# Sch.net
KiCad netlist of a schematic drawn in Altium Designer
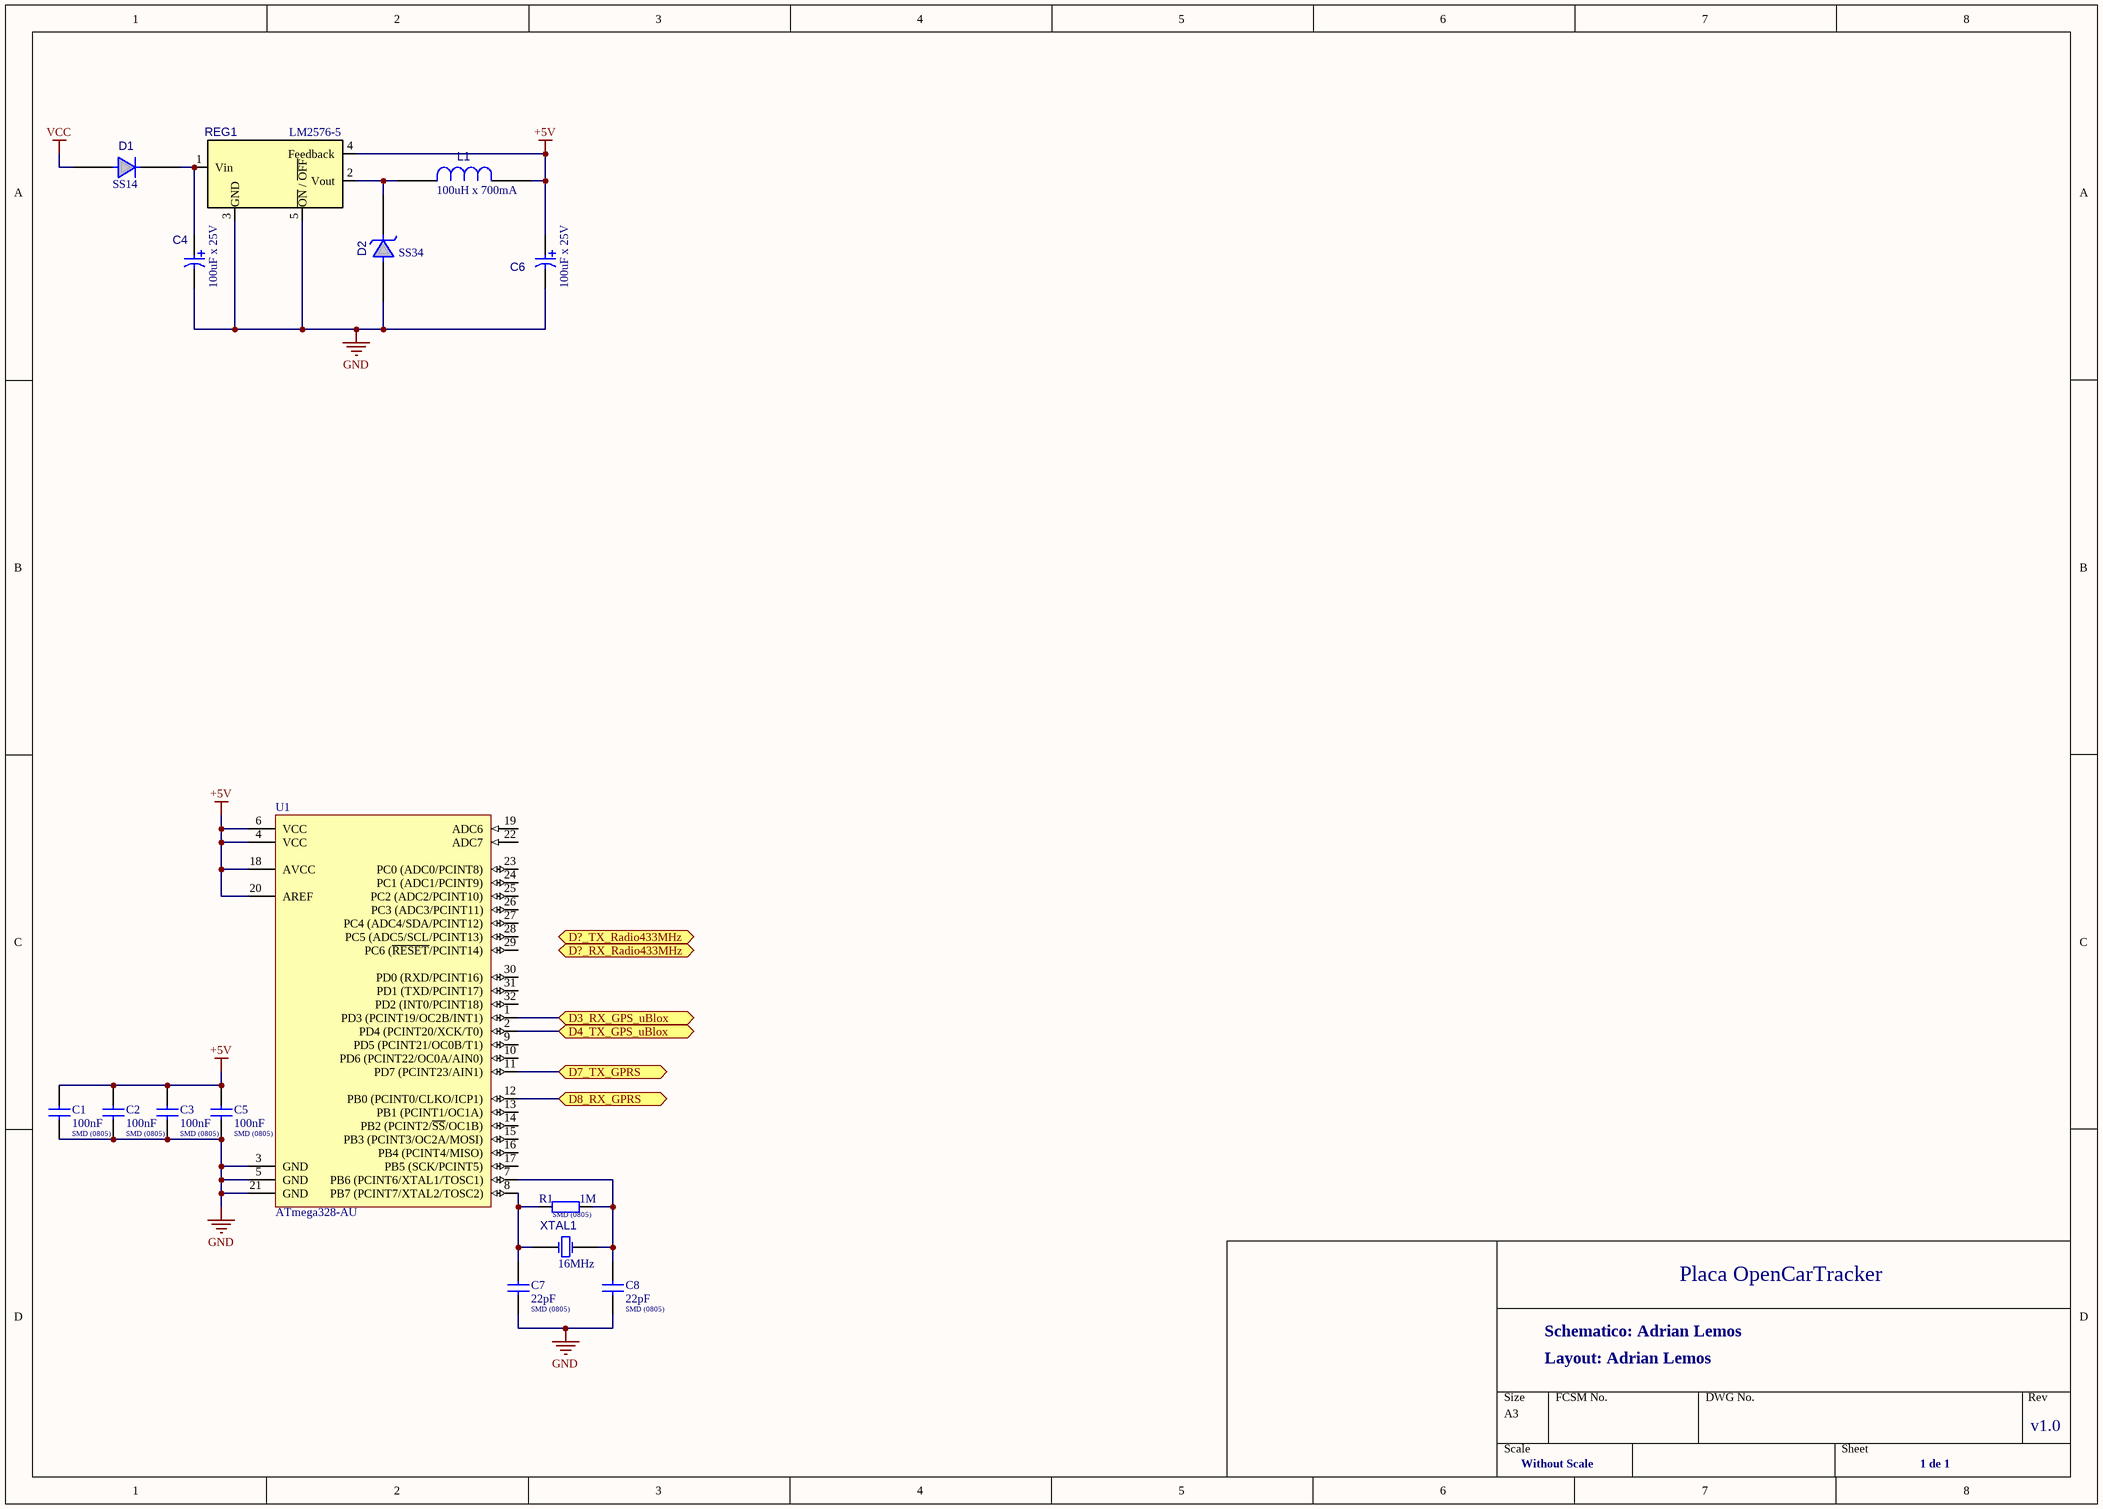
[diagram p0: Sch_.SchDoc]

(export (version "E")
  (design (tool "Eeschema 10.0.6"))
  (components
    (comp (ref "C1")
      (value "Capacitor SMD")
      (footprint "CAP_0805")
      (fields (field (name "VALOR") "100nF") (field (name "ENCAPSULAMENTO") "SMD (0805)"))
      (libsource (lib "Altium_Library_Brasil") (part "Capacitor SMD"))
    )
    (comp (ref "C2")
      (value "Capacitor SMD")
      (footprint "CAP_0805")
      (fields (field (name "VALOR") "100nF") (field (name "ENCAPSULAMENTO") "SMD (0805)"))
      (libsource (lib "Altium_Library_Brasil") (part "Capacitor SMD"))
    )
    (comp (ref "C3")
      (value "Capacitor SMD")
      (footprint "CAP_0805")
      (fields (field (name "VALOR") "100nF") (field (name "ENCAPSULAMENTO") "SMD (0805)"))
      (libsource (lib "Altium_Library_Brasil") (part "Capacitor SMD"))
    )
    (comp (ref "C4")
      (value "Capacitor Eletrolitico")
      (footprint "CAPACITOR ELETROLITICO SMD")
      (fields (field (name "VALOR") "100uF x 25V"))
      (libsource (lib "Altium_Library_Brasil") (part "Capacitor Eletrolitico"))
    )
    (comp (ref "C5")
      (value "Capacitor SMD")
      (footprint "CAP_0805")
      (fields (field (name "VALOR") "100nF") (field (name "ENCAPSULAMENTO") "SMD (0805)"))
      (libsource (lib "Altium_Library_Brasil") (part "Capacitor SMD"))
    )
    (comp (ref "C6")
      (value "Capacitor Eletrolitico")
      (footprint "CAPACITOR ELETROLITICO SMD")
      (fields (field (name "VALOR") "100uF x 25V"))
      (libsource (lib "Altium_Library_Brasil") (part "Capacitor Eletrolitico"))
    )
    (comp (ref "C7")
      (value "Capacitor SMD")
      (footprint "CAP_0805")
      (fields (field (name "VALOR") "22pF") (field (name "ENCAPSULAMENTO") "SMD (0805)"))
      (libsource (lib "Altium_Library_Brasil") (part "Capacitor SMD"))
    )
    (comp (ref "C8")
      (value "Capacitor SMD")
      (footprint "CAP_0805")
      (fields (field (name "VALOR") "22pF") (field (name "ENCAPSULAMENTO") "SMD (0805)"))
      (libsource (lib "Altium_Library_Brasil") (part "Capacitor SMD"))
    )
    (comp (ref "D1")
      (value "DIODO_SS14_S1D")
      (footprint "DO214AC")
      (description "Diodo SMD Shottky")
      (fields (field (name "MODELO") "SS14"))
      (libsource (lib "Altium_Library_Brasil") (part "SS14 Schottky Diode"))
    )
    (comp (ref "D2")
      (value "SS34")
      (footprint "DO214AB")
      (description "DIODO-SCHOTTKY-SMD 3A 40V")
      (fields (field (name "MODELO") "SS34"))
      (libsource (lib "Altium_Library_Brasil") (part "SS34"))
    )
    (comp (ref "L1")
      (value "Indutor_700mA")
      (footprint "INDUTOR RADIAL 10.5MM")
      (description "IND200-CIRC")
      (fields (field (name "VALOR") "100uH x 700mA"))
      (libsource (lib "Altium_Library_Brasil") (part "Indutor_700mA"))
    )
    (comp (ref "R1")
      (value "Resistor SMD")
      (footprint "RES_0805")
      (fields (field (name "VALOR") "1M") (field (name "ENCAPSULAMENTO") "SMD (0805)"))
      (libsource (lib "Altium_Library_Brasil") (part "Resistor SMD"))
    )
    (comp (ref "REG1")
      (value "LM2576")
      (footprint "TO-263-5")
      (description "Regulador de Tensão LM2576")
      (fields (field (name "MODELO") "LM2576-5"))
      (libsource (lib "Altium_Library_Brasil") (part "LM2576"))
    )
    (comp (ref "U1")
      (value "ATmega328-AU")
      (footprint "TQFP32")
      (fields (field (name "MODELO") "ATmega328-AU"))
      (libsource (lib "Altium_Library_Brasil") (part "ATmega328-AU"))
    )
    (comp (ref "XTAL1")
      (value "CRISTAL-SMD-HC49S")
      (footprint "Cristal HC49S")
      (fields (field (name "VALOR") "16MHz"))
      (libsource (lib "Altium_Library_Brasil") (part "CRISTAL-SMD-HC49S"))
    )
  )
  (nets
    (net (code "1") (name "+5V") (class "Default")
      (node (ref "C1") (pin "2") (pinfunction "2_2") (pintype "passive"))
      (node (ref "C2") (pin "2") (pinfunction "2_2") (pintype "passive"))
      (node (ref "C3") (pin "2") (pinfunction "2_2") (pintype "passive"))
      (node (ref "C5") (pin "2") (pinfunction "2_2") (pintype "passive"))
      (node (ref "C6") (pin "1") (pinfunction "PLUS_1") (pintype "passive"))
      (node (ref "L1") (pin "1") (pintype "passive"))
      (node (ref "REG1") (pin "4") (pinfunction "Feedback_4") (pintype "passive"))
      (node (ref "U1") (pin "18") (pinfunction "AVCC_18") (pintype "power_in"))
      (node (ref "U1") (pin "20") (pinfunction "AREF_20") (pintype "passive"))
      (node (ref "U1") (pin "4") (pinfunction "VCC_4") (pintype "power_in"))
      (node (ref "U1") (pin "6") (pinfunction "VCC_6") (pintype "power_in"))
    )
    (net (code "2") (name "/D3_RX_GPS_uBlox") (class "Default")
      (node (ref "U1") (pin "1") (pinfunction "PD3_(PCINT19/OC2B/INT1)_1") (pintype "bidirectional"))
    )
    (net (code "3") (name "/D4_TX_GPS_uBlox") (class "Default")
      (node (ref "U1") (pin "2") (pinfunction "PD4_(PCINT20/XCK/T0)_2") (pintype "bidirectional"))
    )
    (net (code "4") (name "/D7_TX_GPRS") (class "Default")
      (node (ref "U1") (pin "11") (pinfunction "PD7_(PCINT23/AIN1)_11") (pintype "bidirectional"))
    )
    (net (code "5") (name "/D8_RX_GPRS") (class "Default")
      (node (ref "U1") (pin "12") (pinfunction "PB0_(PCINT0/CLKO/ICP1)_12") (pintype "bidirectional"))
    )
    (net (code "8") (name "GND") (class "Default")
      (node (ref "C1") (pin "1") (pinfunction "1_1") (pintype "passive"))
      (node (ref "C2") (pin "1") (pinfunction "1_1") (pintype "passive"))
      (node (ref "C3") (pin "1") (pinfunction "1_1") (pintype "passive"))
      (node (ref "C4") (pin "2") (pinfunction "MINUS_2") (pintype "passive"))
      (node (ref "C5") (pin "1") (pinfunction "1_1") (pintype "passive"))
      (node (ref "C6") (pin "2") (pinfunction "MINUS_2") (pintype "passive"))
      (node (ref "C7") (pin "1") (pinfunction "1_1") (pintype "passive"))
      (node (ref "C8") (pin "1") (pinfunction "1_1") (pintype "passive"))
      (node (ref "D2") (pin "1") (pinfunction "1_1") (pintype "passive"))
      (node (ref "REG1") (pin "3") (pinfunction "GND_3") (pintype "passive"))
      (node (ref "REG1") (pin "5") (pinfunction "~{ON}_/_~{OFF}_5") (pintype "passive"))
      (node (ref "U1") (pin "21") (pinfunction "GND_21") (pintype "power_in"))
      (node (ref "U1") (pin "3") (pinfunction "GND_3") (pintype "power_in"))
      (node (ref "U1") (pin "5") (pinfunction "GND_5") (pintype "power_in"))
    )
    (net (code "9") (name "Net-(C4-PLUS)") (class "Default")
      (node (ref "C4") (pin "1") (pinfunction "PLUS_1") (pintype "passive"))
      (node (ref "D1") (pin "1") (pinfunction "K_1") (pintype "passive"))
      (node (ref "REG1") (pin "1") (pinfunction "Vin_1") (pintype "passive"))
    )
    (net (code "10") (name "Net-(REG1-Vout)") (class "Default")
      (node (ref "D2") (pin "2") (pinfunction "2_2") (pintype "passive"))
      (node (ref "L1") (pin "2") (pintype "passive"))
      (node (ref "REG1") (pin "2") (pinfunction "Vout_2") (pintype "passive"))
    )
    (net (code "11") (name "Net-(U1-PB6_(PCINT6{slash}XTAL1{slash}TOSC1))") (class "Default")
      (node (ref "C8") (pin "2") (pinfunction "2_2") (pintype "passive"))
      (node (ref "R1") (pin "2") (pinfunction "2_2") (pintype "passive"))
      (node (ref "U1") (pin "7") (pinfunction "PB6_(PCINT6/XTAL1/TOSC1)_7") (pintype "bidirectional"))
      (node (ref "XTAL1") (pin "2") (pinfunction "OSC2_2") (pintype "passive"))
    )
    (net (code "12") (name "Net-(U1-PB7_(PCINT7{slash}XTAL2{slash}TOSC2))") (class "Default")
      (node (ref "C7") (pin "2") (pinfunction "2_2") (pintype "passive"))
      (node (ref "R1") (pin "1") (pinfunction "1_1") (pintype "passive"))
      (node (ref "U1") (pin "8") (pinfunction "PB7_(PCINT7/XTAL2/TOSC2)_8") (pintype "bidirectional"))
      (node (ref "XTAL1") (pin "1") (pinfunction "OSC1_1") (pintype "passive"))
    )
    (net (code "13") (name "VCC") (class "Default")
      (node (ref "D1") (pin "2") (pinfunction "A_2") (pintype "passive"))
    )
    (net (code "14") (name "unconnected-(U1-ADC6-Pad19)") (class "Default")
      (node (ref "U1") (pin "19") (pinfunction "ADC6_19") (pintype "input"))
    )
    (net (code "15") (name "unconnected-(U1-ADC7-Pad22)") (class "Default")
      (node (ref "U1") (pin "22") (pinfunction "ADC7_22") (pintype "input"))
    )
    (net (code "16") (name "unconnected-(U1-PB1_(PCINT1{slash}OC1A)-Pad13)") (class "Default")
      (node (ref "U1") (pin "13") (pinfunction "PB1_(PCINT1/OC1A)_13") (pintype "bidirectional"))
    )
    (net (code "17") (name "unconnected-(U1-PB2_(PCINT2{slash}~{SS}{slash}OC1B)-Pad14)") (class "Default")
      (node (ref "U1") (pin "14") (pinfunction "PB2_(PCINT2/~{SS}/OC1B)_14") (pintype "bidirectional"))
    )
    (net (code "18") (name "unconnected-(U1-PB3_(PCINT3{slash}OC2A{slash}MOSI)-Pad15)") (class "Default")
      (node (ref "U1") (pin "15") (pinfunction "PB3_(PCINT3/OC2A/MOSI)_15") (pintype "bidirectional"))
    )
    (net (code "19") (name "unconnected-(U1-PB4_(PCINT4{slash}MISO)-Pad16)") (class "Default")
      (node (ref "U1") (pin "16") (pinfunction "PB4_(PCINT4/MISO)_16") (pintype "bidirectional"))
    )
    (net (code "20") (name "unconnected-(U1-PB5_(SCK{slash}PCINT5)-Pad17)") (class "Default")
      (node (ref "U1") (pin "17") (pinfunction "PB5_(SCK/PCINT5)_17") (pintype "bidirectional"))
    )
    (net (code "21") (name "unconnected-(U1-PC0_(ADC0{slash}PCINT8)-Pad23)") (class "Default")
      (node (ref "U1") (pin "23") (pinfunction "PC0_(ADC0/PCINT8)_23") (pintype "bidirectional"))
    )
    (net (code "22") (name "unconnected-(U1-PC1_(ADC1{slash}PCINT9)-Pad24)") (class "Default")
      (node (ref "U1") (pin "24") (pinfunction "PC1_(ADC1/PCINT9)_24") (pintype "bidirectional"))
    )
    (net (code "23") (name "unconnected-(U1-PC2_(ADC2{slash}PCINT10)-Pad25)") (class "Default")
      (node (ref "U1") (pin "25") (pinfunction "PC2_(ADC2/PCINT10)_25") (pintype "bidirectional"))
    )
    (net (code "24") (name "unconnected-(U1-PC3_(ADC3{slash}PCINT11)-Pad26)") (class "Default")
      (node (ref "U1") (pin "26") (pinfunction "PC3_(ADC3/PCINT11)_26") (pintype "bidirectional"))
    )
    (net (code "25") (name "unconnected-(U1-PC4_(ADC4{slash}SDA{slash}PCINT12)-Pad27)") (class "Default")
      (node (ref "U1") (pin "27") (pinfunction "PC4_(ADC4/SDA/PCINT12)_27") (pintype "bidirectional"))
    )
    (net (code "26") (name "unconnected-(U1-PC5_(ADC5{slash}SCL{slash}PCINT13)-Pad28)") (class "Default")
      (node (ref "U1") (pin "28") (pinfunction "PC5_(ADC5/SCL/PCINT13)_28") (pintype "bidirectional"))
    )
    (net (code "27") (name "unconnected-(U1-PC6_(~{RESET}{slash}PCINT14)-Pad29)") (class "Default")
      (node (ref "U1") (pin "29") (pinfunction "PC6_(~{RESET}/PCINT14)_29") (pintype "bidirectional"))
    )
    (net (code "28") (name "unconnected-(U1-PD0_(RXD{slash}PCINT16)-Pad30)") (class "Default")
      (node (ref "U1") (pin "30") (pinfunction "PD0_(RXD/PCINT16)_30") (pintype "bidirectional"))
    )
    (net (code "29") (name "unconnected-(U1-PD1_(TXD{slash}PCINT17)-Pad31)") (class "Default")
      (node (ref "U1") (pin "31") (pinfunction "PD1_(TXD/PCINT17)_31") (pintype "bidirectional"))
    )
    (net (code "30") (name "unconnected-(U1-PD2_(INT0{slash}PCINT18)-Pad32)") (class "Default")
      (node (ref "U1") (pin "32") (pinfunction "PD2_(INT0/PCINT18)_32") (pintype "bidirectional"))
    )
    (net (code "31") (name "unconnected-(U1-PD5_(PCINT21{slash}OC0B{slash}T1)-Pad9)") (class "Default")
      (node (ref "U1") (pin "9") (pinfunction "PD5_(PCINT21/OC0B/T1)_9") (pintype "bidirectional"))
    )
    (net (code "32") (name "unconnected-(U1-PD6_(PCINT22{slash}OC0A{slash}AIN0)-Pad10)") (class "Default")
      (node (ref "U1") (pin "10") (pinfunction "PD6_(PCINT22/OC0A/AIN0)_10") (pintype "bidirectional"))
    )
  )
)
